# emonTx4-ESP8266.net
KiCad netlist of a schematic drawn in EAGLE
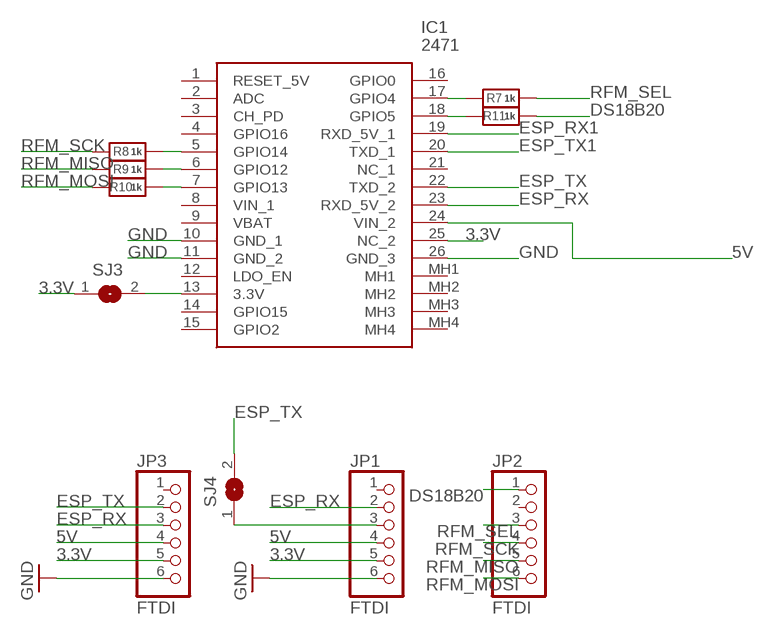
[diagram p0: schematic, sheet 1]

(export (version "E")
  (design (tool "Eeschema 10.0.6"))
  (components
    (comp (ref "IC1")
      (value "2471")
      (footprint "eagle-import:2471")
      (fields (field (name "MOUSER_PART_NUMBER") "485-2471"))
      (libsource (lib "eagle-import") (part "2471"))
    )
    (comp (ref "JP1")
      (value "FTDI")
      (footprint "eagle-import:1X06_ROUND_70")
      (libsource (lib "eagle-import") (part "HEADER-1X670MIL"))
    )
    (comp (ref "JP2")
      (value "FTDI")
      (footprint "eagle-import:1X06_ROUND_70")
      (libsource (lib "eagle-import") (part "HEADER-1X670MIL"))
    )
    (comp (ref "JP3")
      (value "FTDI")
      (footprint "eagle-import:1X06_ROUND_70")
      (libsource (lib "eagle-import") (part "HEADER-1X670MIL"))
    )
    (comp (ref "R7")
      (value "1k")
      (footprint "eagle-import:_0603")
      (libsource (lib "eagle-import") (part "RESISTOR_0603"))
    )
    (comp (ref "R8")
      (value "1k")
      (footprint "eagle-import:_0603")
      (libsource (lib "eagle-import") (part "RESISTOR_0603"))
    )
    (comp (ref "R9")
      (value "1k")
      (footprint "eagle-import:_0603")
      (libsource (lib "eagle-import") (part "RESISTOR_0603"))
    )
    (comp (ref "R10")
      (value "1k")
      (footprint "eagle-import:_0603")
      (libsource (lib "eagle-import") (part "RESISTOR_0603"))
    )
    (comp (ref "R11")
      (value "1k")
      (footprint "eagle-import:_0603")
      (libsource (lib "eagle-import") (part "RESISTOR_0603"))
    )
    (comp (ref "SJ3") (value "SJ") (footprint "eagle-import:SJ") (libsource (lib "eagle-import") (part "SJ")))
    (comp (ref "SJ4") (value "SJ") (footprint "eagle-import:SJ") (libsource (lib "eagle-import") (part "SJ")))
  )
  (nets
    (net (code "1") (name "/3.3V") (class "Default")
      (node (ref "IC1") (pin "25") (pinfunction "NC_2_25") (pintype "bidirectional"))
      (node (ref "JP1") (pin "5") (pinfunction "5_5") (pintype "passive"))
      (node (ref "JP3") (pin "5") (pinfunction "5_5") (pintype "passive"))
      (node (ref "SJ3") (pin "1") (pinfunction "1_1") (pintype "passive"))
    )
    (net (code "2") (name "/5V") (class "Default")
      (node (ref "IC1") (pin "24") (pinfunction "VIN_2_24") (pintype "bidirectional"))
      (node (ref "JP1") (pin "4") (pinfunction "4_4") (pintype "passive"))
      (node (ref "JP3") (pin "4") (pinfunction "4_4") (pintype "passive"))
    )
    (net (code "3") (name "/DS18B20") (class "Default")
      (node (ref "JP2") (pin "1") (pinfunction "1_1") (pintype "passive"))
      (node (ref "R11") (pin "1") (pinfunction "1_1") (pintype "passive"))
    )
    (net (code "4") (name "/ESP_RX") (class "Default")
      (node (ref "IC1") (pin "23") (pinfunction "RXD_5V_2_23") (pintype "bidirectional"))
      (node (ref "JP1") (pin "2") (pinfunction "2_2") (pintype "passive"))
      (node (ref "JP3") (pin "3") (pinfunction "3_3") (pintype "passive"))
    )
    (net (code "5") (name "/ESP_RX1") (class "Default")
      (node (ref "IC1") (pin "19") (pinfunction "RXD_5V_1_19") (pintype "bidirectional"))
    )
    (net (code "6") (name "/ESP_TX") (class "Default")
      (node (ref "IC1") (pin "22") (pinfunction "TXD_2_22") (pintype "bidirectional"))
      (node (ref "JP3") (pin "2") (pinfunction "2_2") (pintype "passive"))
      (node (ref "SJ4") (pin "2") (pinfunction "2_2") (pintype "passive"))
    )
    (net (code "7") (name "/ESP_TX1") (class "Default")
      (node (ref "IC1") (pin "20") (pinfunction "TXD_1_20") (pintype "bidirectional"))
    )
    (net (code "8") (name "/RFM_MISO") (class "Default")
      (node (ref "JP2") (pin "5") (pinfunction "5_5") (pintype "passive"))
      (node (ref "R9") (pin "2") (pinfunction "2_2") (pintype "passive"))
    )
    (net (code "9") (name "/RFM_MOSI") (class "Default")
      (node (ref "JP2") (pin "6") (pinfunction "6_6") (pintype "passive"))
      (node (ref "R10") (pin "2") (pinfunction "2_2") (pintype "passive"))
    )
    (net (code "10") (name "/RFM_SCK") (class "Default")
      (node (ref "JP2") (pin "4") (pinfunction "4_4") (pintype "passive"))
      (node (ref "R8") (pin "2") (pinfunction "2_2") (pintype "passive"))
    )
    (net (code "11") (name "/RFM_SEL") (class "Default")
      (node (ref "JP2") (pin "3") (pinfunction "3_3") (pintype "passive"))
      (node (ref "R7") (pin "1") (pinfunction "1_1") (pintype "passive"))
    )
    (net (code "12") (name "GND") (class "Default")
      (node (ref "IC1") (pin "10") (pinfunction "GND_1_10") (pintype "bidirectional"))
      (node (ref "IC1") (pin "11") (pinfunction "GND_2_11") (pintype "bidirectional"))
      (node (ref "IC1") (pin "26") (pinfunction "GND_3_26") (pintype "bidirectional"))
      (node (ref "JP1") (pin "6") (pinfunction "6_6") (pintype "passive"))
      (node (ref "JP3") (pin "6") (pinfunction "6_6") (pintype "passive"))
    )
    (net (code "13") (name "Net-(IC1-3.3V)") (class "Default")
      (node (ref "IC1") (pin "13") (pinfunction "3.3V_13") (pintype "bidirectional"))
      (node (ref "SJ3") (pin "2") (pinfunction "2_2") (pintype "passive"))
    )
    (net (code "14") (name "Net-(IC1-GPIO4)") (class "Default")
      (node (ref "IC1") (pin "17") (pinfunction "GPIO4_17") (pintype "bidirectional"))
      (node (ref "R7") (pin "2") (pinfunction "2_2") (pintype "passive"))
    )
    (net (code "15") (name "Net-(IC1-GPIO5)") (class "Default")
      (node (ref "IC1") (pin "18") (pinfunction "GPIO5_18") (pintype "bidirectional"))
      (node (ref "R11") (pin "2") (pinfunction "2_2") (pintype "passive"))
    )
    (net (code "16") (name "Net-(IC1-GPIO12)") (class "Default")
      (node (ref "IC1") (pin "6") (pinfunction "GPIO12_6") (pintype "bidirectional"))
      (node (ref "R9") (pin "1") (pinfunction "1_1") (pintype "passive"))
    )
    (net (code "17") (name "Net-(IC1-GPIO13)") (class "Default")
      (node (ref "IC1") (pin "7") (pinfunction "GPIO13_7") (pintype "bidirectional"))
      (node (ref "R10") (pin "1") (pinfunction "1_1") (pintype "passive"))
    )
    (net (code "18") (name "Net-(IC1-GPIO14)") (class "Default")
      (node (ref "IC1") (pin "5") (pinfunction "GPIO14_5") (pintype "bidirectional"))
      (node (ref "R8") (pin "1") (pinfunction "1_1") (pintype "passive"))
    )
    (net (code "19") (name "Net-(JP1-Pad3)") (class "Default")
      (node (ref "JP1") (pin "3") (pinfunction "3_3") (pintype "passive"))
      (node (ref "SJ4") (pin "1") (pinfunction "1_1") (pintype "passive"))
    )
    (net (code "20") (name "unconnected-(IC1-ADC-Pad2)") (class "Default")
      (node (ref "IC1") (pin "2") (pinfunction "ADC_2") (pintype "bidirectional"))
    )
    (net (code "21") (name "unconnected-(IC1-CH_PD-Pad3)") (class "Default")
      (node (ref "IC1") (pin "3") (pinfunction "CH_PD_3") (pintype "bidirectional"))
    )
    (net (code "22") (name "unconnected-(IC1-GPIO0-Pad16)") (class "Default")
      (node (ref "IC1") (pin "16") (pinfunction "GPIO0_16") (pintype "bidirectional"))
    )
    (net (code "23") (name "unconnected-(IC1-GPIO2-Pad15)") (class "Default")
      (node (ref "IC1") (pin "15") (pinfunction "GPIO2_15") (pintype "bidirectional"))
    )
    (net (code "24") (name "unconnected-(IC1-GPIO15-Pad14)") (class "Default")
      (node (ref "IC1") (pin "14") (pinfunction "GPIO15_14") (pintype "bidirectional"))
    )
    (net (code "25") (name "unconnected-(IC1-GPIO16-Pad4)") (class "Default")
      (node (ref "IC1") (pin "4") (pinfunction "GPIO16_4") (pintype "bidirectional"))
    )
    (net (code "26") (name "unconnected-(IC1-LDO_EN-Pad12)") (class "Default")
      (node (ref "IC1") (pin "12") (pinfunction "LDO_EN_12") (pintype "bidirectional"))
    )
    (net (code "27") (name "unconnected-(IC1-NC_1-Pad21)") (class "Default")
      (node (ref "IC1") (pin "21") (pinfunction "NC_1_21") (pintype "bidirectional"))
    )
    (net (code "28") (name "unconnected-(IC1-PadMH1)") (class "Default")
      (node (ref "IC1") (pin "MH1") (pinfunction "MH1_MH1") (pintype "bidirectional"))
    )
    (net (code "29") (name "unconnected-(IC1-PadMH2)") (class "Default")
      (node (ref "IC1") (pin "MH2") (pinfunction "MH2_MH2") (pintype "bidirectional"))
    )
    (net (code "30") (name "unconnected-(IC1-PadMH3)") (class "Default")
      (node (ref "IC1") (pin "MH3") (pinfunction "MH3_MH3") (pintype "bidirectional"))
    )
    (net (code "31") (name "unconnected-(IC1-PadMH4)") (class "Default")
      (node (ref "IC1") (pin "MH4") (pinfunction "MH4_MH4") (pintype "bidirectional"))
    )
    (net (code "32") (name "unconnected-(IC1-RESET_5V-Pad1)") (class "Default")
      (node (ref "IC1") (pin "1") (pinfunction "RESET_5V_1") (pintype "bidirectional"))
    )
    (net (code "33") (name "unconnected-(IC1-VBAT-Pad9)") (class "Default")
      (node (ref "IC1") (pin "9") (pinfunction "VBAT_9") (pintype "bidirectional"))
    )
    (net (code "34") (name "unconnected-(IC1-VIN_1-Pad8)") (class "Default")
      (node (ref "IC1") (pin "8") (pinfunction "VIN_1_8") (pintype "bidirectional"))
    )
    (net (code "35") (name "unconnected-(JP1-Pad1)") (class "Default")
      (node (ref "JP1") (pin "1") (pinfunction "1_1") (pintype "passive"))
    )
    (net (code "36") (name "unconnected-(JP2-Pad2)") (class "Default")
      (node (ref "JP2") (pin "2") (pinfunction "2_2") (pintype "passive"))
    )
    (net (code "37") (name "unconnected-(JP3-Pad1)") (class "Default")
      (node (ref "JP3") (pin "1") (pinfunction "1_1") (pintype "passive"))
    )
  )
)
